# MachChinh.net
KiCad netlist of a schematic drawn in Altium Designer
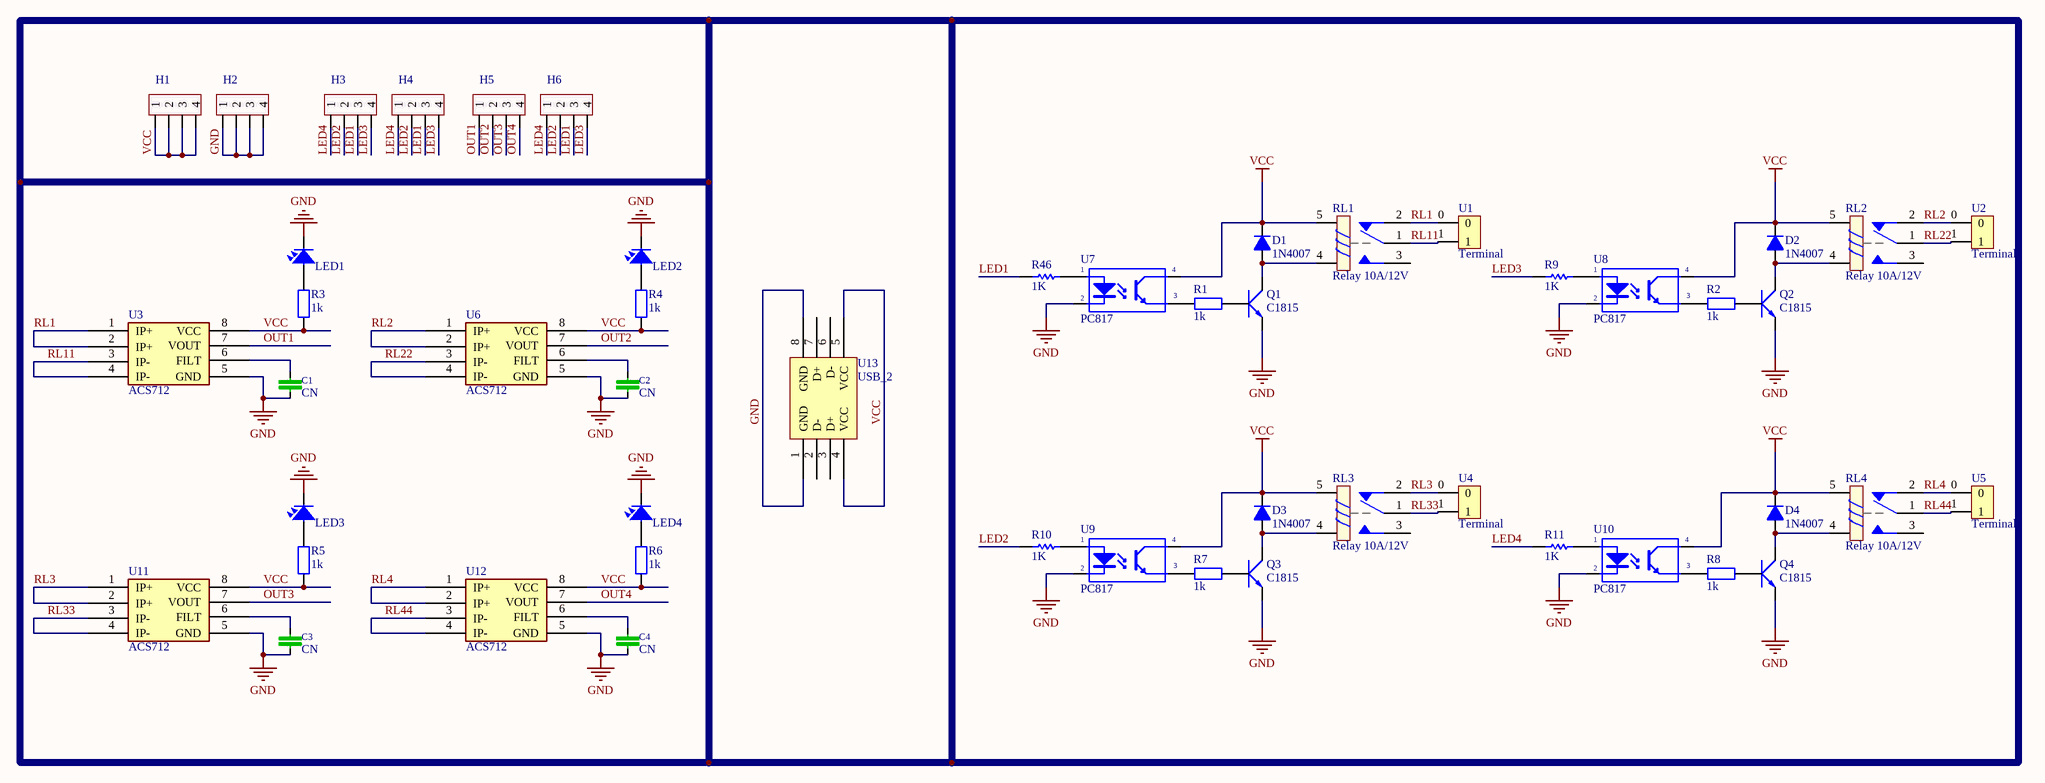
[diagram p0: MachChinh.SchDoc]

(export (version "E")
  (design (tool "Eeschema 10.0.6"))
  (components
    (comp (ref "C1")
      (value "CN")
      (footprint "C020-020,040")
      (description "CAP CER 0.047UF 25V X7R 0402")
      (libsource (lib "LIBRARY") (part "CN"))
    )
    (comp (ref "C2")
      (value "CN")
      (footprint "C020-020,040")
      (description "CAP CER 0.047UF 25V X7R 0402")
      (libsource (lib "LIBRARY") (part "CN"))
    )
    (comp (ref "C3")
      (value "CN")
      (footprint "C020-020,040")
      (description "CAP CER 0.047UF 25V X7R 0402")
      (libsource (lib "LIBRARY") (part "CN"))
    )
    (comp (ref "C4")
      (value "CN")
      (footprint "C020-020,040")
      (description "CAP CER 0.047UF 25V X7R 0402")
      (libsource (lib "LIBRARY") (part "CN"))
    )
    (comp (ref "D1")
      (value "1N4007")
      (footprint "D1A")
      (description "Diode 1A")
      (libsource (lib "syhaunguyen") (part "D1A"))
    )
    (comp (ref "D2")
      (value "1N4007")
      (footprint "D1A")
      (description "Diode 1A")
      (libsource (lib "syhaunguyen") (part "D1A"))
    )
    (comp (ref "D3")
      (value "1N4007")
      (footprint "D1A")
      (description "Diode 1A")
      (libsource (lib "syhaunguyen") (part "D1A"))
    )
    (comp (ref "D4")
      (value "1N4007")
      (footprint "D1A")
      (description "Diode 1A")
      (libsource (lib "syhaunguyen") (part "D1A"))
    )
    (comp (ref "H1")
      (value "Header4")
      (footprint "Header4")
      (description "Header IDC, 4 x 1 Pin Vertical 2.54mm Pitch (Non-Boxed, Male)")
      (libsource (lib "LIBRARY") (part "Header4"))
    )
    (comp (ref "H2")
      (value "Header4")
      (footprint "Header4")
      (description "Header IDC, 4 x 1 Pin Vertical 2.54mm Pitch (Non-Boxed, Male)")
      (libsource (lib "LIBRARY") (part "Header4"))
    )
    (comp (ref "H3")
      (value "Header4")
      (footprint "Header4")
      (description "Header IDC, 4 x 1 Pin Vertical 2.54mm Pitch (Non-Boxed, Male)")
      (libsource (lib "LIBRARY") (part "Header4"))
    )
    (comp (ref "H4")
      (value "Header4")
      (footprint "Header4")
      (description "Header IDC, 4 x 1 Pin Vertical 2.54mm Pitch (Non-Boxed, Male)")
      (libsource (lib "LIBRARY") (part "Header4"))
    )
    (comp (ref "H5")
      (value "Header4")
      (footprint "Header4")
      (description "Header IDC, 4 x 1 Pin Vertical 2.54mm Pitch (Non-Boxed, Male)")
      (libsource (lib "LIBRARY") (part "Header4"))
    )
    (comp (ref "H6")
      (value "Header4")
      (footprint "Header4")
      (description "Header IDC, 4 x 1 Pin Vertical 2.54mm Pitch (Non-Boxed, Male)")
      (libsource (lib "LIBRARY") (part "Header4"))
    )
    (comp (ref "LED1")
      (value "LED")
      (footprint "LED-3")
      (description "LED Single colour Green and Red")
      (libsource (lib "syhaunguyen") (part "LED"))
    )
    (comp (ref "LED2")
      (value "LED")
      (footprint "LED-3")
      (description "LED Single colour Green and Red")
      (libsource (lib "syhaunguyen") (part "LED"))
    )
    (comp (ref "LED3")
      (value "LED")
      (footprint "LED-3")
      (description "LED Single colour Green and Red")
      (libsource (lib "syhaunguyen") (part "LED"))
    )
    (comp (ref "LED4")
      (value "LED")
      (footprint "LED-3")
      (description "LED Single colour Green and Red")
      (libsource (lib "syhaunguyen") (part "LED"))
    )
    (comp (ref "Q1")
      (value "C1815")
      (footprint "QTO-92")
      (description "NPN 600mW, ECB")
      (libsource (lib "syhaunguyen") (part "C1815"))
    )
    (comp (ref "Q2")
      (value "C1815")
      (footprint "QTO-92")
      (description "NPN 600mW, ECB")
      (libsource (lib "syhaunguyen") (part "C1815"))
    )
    (comp (ref "Q3")
      (value "C1815")
      (footprint "QTO-92")
      (description "NPN 600mW, ECB")
      (libsource (lib "syhaunguyen") (part "C1815"))
    )
    (comp (ref "Q4")
      (value "C1815")
      (footprint "QTO-92")
      (description "NPN 600mW, ECB")
      (libsource (lib "syhaunguyen") (part "C1815"))
    )
    (comp (ref "R1")
      (value "1k")
      (footprint "R1/4W")
      (description "Resistor 1/4W")
      (libsource (lib "syhaunguyen") (part "R1/4W"))
    )
    (comp (ref "R2")
      (value "1k")
      (footprint "R1/4W")
      (description "Resistor 1/4W")
      (libsource (lib "syhaunguyen") (part "R1/4W"))
    )
    (comp (ref "R3")
      (value "1k")
      (footprint "R1/4W")
      (description "Resistor 1/4W")
      (libsource (lib "syhaunguyen") (part "R1/4W"))
    )
    (comp (ref "R4")
      (value "1k")
      (footprint "R1/4W")
      (description "Resistor 1/4W")
      (libsource (lib "syhaunguyen") (part "R1/4W"))
    )
    (comp (ref "R5")
      (value "1k")
      (footprint "R1/4W")
      (description "Resistor 1/4W")
      (libsource (lib "syhaunguyen") (part "R1/4W"))
    )
    (comp (ref "R6")
      (value "1k")
      (footprint "R1/4W")
      (description "Resistor 1/4W")
      (libsource (lib "syhaunguyen") (part "R1/4W"))
    )
    (comp (ref "R7")
      (value "1k")
      (footprint "R1/4W")
      (description "Resistor 1/4W")
      (libsource (lib "syhaunguyen") (part "R1/4W"))
    )
    (comp (ref "R8")
      (value "1k")
      (footprint "R1/4W")
      (description "Resistor 1/4W")
      (libsource (lib "syhaunguyen") (part "R1/4W"))
    )
    (comp (ref "R9")
      (value "1K")
      (footprint "R1/4W")
      (description "Resistor")
      (fields
        (field (name "MANUFACTURER") "Generic Components")
        (field (name "Comment") "Res1")
        (field (name "PUBLISHER") "Altium Hobart Technology Centre")
      )
      (libsource (lib "syhaunguyen") (part "Res1_4"))
    )
    (comp (ref "R10")
      (value "1K")
      (footprint "R1/4W")
      (description "Resistor")
      (fields
        (field (name "MANUFACTURER") "Generic Components")
        (field (name "Comment") "Res1")
        (field (name "PUBLISHER") "Altium Hobart Technology Centre")
      )
      (libsource (lib "syhaunguyen") (part "Res1_4"))
    )
    (comp (ref "R11")
      (value "1K")
      (footprint "R1/4W")
      (description "Resistor")
      (fields
        (field (name "MANUFACTURER") "Generic Components")
        (field (name "Comment") "Res1")
        (field (name "PUBLISHER") "Altium Hobart Technology Centre")
      )
      (libsource (lib "syhaunguyen") (part "Res1_4"))
    )
    (comp (ref "R46")
      (value "1K")
      (footprint "R1/4W")
      (description "Resistor")
      (fields
        (field (name "MANUFACTURER") "Generic Components")
        (field (name "Comment") "Res1")
        (field (name "PUBLISHER") "Altium Hobart Technology Centre")
      )
      (libsource (lib "syhaunguyen") (part "Res1_4"))
    )
    (comp (ref "RL1")
      (value "Relay 10A/12V")
      (footprint "RL_SPDT_10A")
      (description "Relay SPDT,10A - 12VDC 5 Pin")
      (libsource (lib "syhaunguyen") (part "Relay 1"))
    )
    (comp (ref "RL2")
      (value "Relay 10A/12V")
      (footprint "RL_SPDT_10A")
      (description "Relay SPDT,10A - 12VDC 5 Pin")
      (libsource (lib "syhaunguyen") (part "Relay 1"))
    )
    (comp (ref "RL3")
      (value "Relay 10A/12V")
      (footprint "RL_SPDT_10A")
      (description "Relay SPDT,10A - 12VDC 5 Pin")
      (libsource (lib "syhaunguyen") (part "Relay 1"))
    )
    (comp (ref "RL4")
      (value "Relay 10A/12V")
      (footprint "RL_SPDT_10A")
      (description "Relay SPDT,10A - 12VDC 5 Pin")
      (libsource (lib "syhaunguyen") (part "Relay 1"))
    )
    (comp (ref "U1")
      (value "Terminal")
      (footprint "TERMINAL5.08")
      (libsource (lib "THU_VIEN_PQB_Schlib1") (part "TERMINAL5.08"))
    )
    (comp (ref "U2")
      (value "Terminal")
      (footprint "TERMINAL5.08")
      (libsource (lib "THU_VIEN_PQB_Schlib1") (part "TERMINAL5.08"))
    )
    (comp (ref "U3")
      (value "ACS712")
      (footprint "ACS712")
      (libsource (lib "THU_VIEN_PQB_Schlib1") (part "ACS712"))
    )
    (comp (ref "U4")
      (value "Terminal")
      (footprint "TERMINAL5.08")
      (libsource (lib "THU_VIEN_PQB_Schlib1") (part "TERMINAL5.08"))
    )
    (comp (ref "U5")
      (value "Terminal")
      (footprint "TERMINAL5.08")
      (libsource (lib "THU_VIEN_PQB_Schlib1") (part "TERMINAL5.08"))
    )
    (comp (ref "U6")
      (value "ACS712")
      (footprint "ACS712")
      (libsource (lib "THU_VIEN_PQB_Schlib1") (part "ACS712"))
    )
    (comp (ref "U7")
      (value "PC817")
      (footprint "DIP4/W0.3")
      (description "Single Opto")
      (libsource (lib "syhaunguyen") (part "PC817"))
    )
    (comp (ref "U8")
      (value "PC817")
      (footprint "DIP4/W0.3")
      (description "Single Opto")
      (libsource (lib "syhaunguyen") (part "PC817"))
    )
    (comp (ref "U9")
      (value "PC817")
      (footprint "DIP4/W0.3")
      (description "Single Opto")
      (libsource (lib "syhaunguyen") (part "PC817"))
    )
    (comp (ref "U10")
      (value "PC817")
      (footprint "DIP4/W0.3")
      (description "Single Opto")
      (libsource (lib "syhaunguyen") (part "PC817"))
    )
    (comp (ref "U11")
      (value "ACS712")
      (footprint "ACS712")
      (libsource (lib "THU_VIEN_PQB_Schlib1") (part "ACS712"))
    )
    (comp (ref "U12")
      (value "ACS712")
      (footprint "ACS712")
      (libsource (lib "THU_VIEN_PQB_Schlib1") (part "ACS712"))
    )
    (comp (ref "U13")
      (value "USB_2")
      (footprint "USB_2")
      (description "USB")
      (libsource (lib "THU_VIEN_PQB_Schlib1") (part "USB_2"))
    )
  )
  (nets
    (net (code "1") (name "/LED1") (class "Default")
      (node (ref "H3") (pin "3") (pinfunction "3_3") (pintype "passive"))
      (node (ref "H4") (pin "3") (pinfunction "3_3") (pintype "passive"))
      (node (ref "H6") (pin "3") (pinfunction "3_3") (pintype "passive"))
      (node (ref "R46") (pin "2") (pinfunction "2_2") (pintype "passive"))
    )
    (net (code "2") (name "/LED2") (class "Default")
      (node (ref "H3") (pin "2") (pinfunction "2_2") (pintype "passive"))
      (node (ref "H4") (pin "2") (pinfunction "2_2") (pintype "passive"))
      (node (ref "H6") (pin "2") (pinfunction "2_2") (pintype "passive"))
      (node (ref "R10") (pin "2") (pinfunction "2_2") (pintype "passive"))
    )
    (net (code "3") (name "/LED3") (class "Default")
      (node (ref "H3") (pin "4") (pinfunction "4_4") (pintype "passive"))
      (node (ref "H4") (pin "4") (pinfunction "4_4") (pintype "passive"))
      (node (ref "H6") (pin "4") (pinfunction "4_4") (pintype "passive"))
      (node (ref "R9") (pin "2") (pinfunction "2_2") (pintype "passive"))
    )
    (net (code "4") (name "/LED4") (class "Default")
      (node (ref "H3") (pin "1") (pinfunction "1_1") (pintype "passive"))
      (node (ref "H4") (pin "1") (pinfunction "1_1") (pintype "passive"))
      (node (ref "H6") (pin "1") (pinfunction "1_1") (pintype "passive"))
      (node (ref "R11") (pin "2") (pinfunction "2_2") (pintype "passive"))
    )
    (net (code "5") (name "/OUT1") (class "Default")
      (node (ref "H5") (pin "1") (pinfunction "1_1") (pintype "passive"))
      (node (ref "U3") (pin "7") (pinfunction "VOUT_7") (pintype "passive"))
    )
    (net (code "6") (name "/OUT2") (class "Default")
      (node (ref "H5") (pin "2") (pinfunction "2_2") (pintype "passive"))
      (node (ref "U6") (pin "7") (pinfunction "VOUT_7") (pintype "passive"))
    )
    (net (code "7") (name "/OUT3") (class "Default")
      (node (ref "H5") (pin "3") (pinfunction "3_3") (pintype "passive"))
      (node (ref "U11") (pin "7") (pinfunction "VOUT_7") (pintype "passive"))
    )
    (net (code "8") (name "/OUT4") (class "Default")
      (node (ref "H5") (pin "4") (pinfunction "4_4") (pintype "passive"))
      (node (ref "U12") (pin "7") (pinfunction "VOUT_7") (pintype "passive"))
    )
    (net (code "9") (name "/RL1") (class "Default")
      (node (ref "RL1") (pin "2") (pinfunction "2_2") (pintype "passive"))
      (node (ref "U1") (pin "0") (pinfunction "0_0") (pintype "passive"))
      (node (ref "U3") (pin "1") (pinfunction "IP+_1") (pintype "passive"))
      (node (ref "U3") (pin "2") (pinfunction "IP+_2") (pintype "passive"))
    )
    (net (code "10") (name "/RL2") (class "Default")
      (node (ref "RL2") (pin "2") (pinfunction "2_2") (pintype "passive"))
      (node (ref "U2") (pin "0") (pinfunction "0_0") (pintype "passive"))
      (node (ref "U6") (pin "1") (pinfunction "IP+_1") (pintype "passive"))
      (node (ref "U6") (pin "2") (pinfunction "IP+_2") (pintype "passive"))
    )
    (net (code "11") (name "/RL3") (class "Default")
      (node (ref "RL3") (pin "2") (pinfunction "2_2") (pintype "passive"))
      (node (ref "U11") (pin "1") (pinfunction "IP+_1") (pintype "passive"))
      (node (ref "U11") (pin "2") (pinfunction "IP+_2") (pintype "passive"))
      (node (ref "U4") (pin "0") (pinfunction "0_0") (pintype "passive"))
    )
    (net (code "12") (name "/RL4") (class "Default")
      (node (ref "RL4") (pin "2") (pinfunction "2_2") (pintype "passive"))
      (node (ref "U12") (pin "1") (pinfunction "IP+_1") (pintype "passive"))
      (node (ref "U12") (pin "2") (pinfunction "IP+_2") (pintype "passive"))
      (node (ref "U5") (pin "0") (pinfunction "0_0") (pintype "passive"))
    )
    (net (code "13") (name "/RL11") (class "Default")
      (node (ref "RL1") (pin "1") (pinfunction "1_1") (pintype "passive"))
      (node (ref "U1") (pin "1") (pinfunction "1_1") (pintype "passive"))
      (node (ref "U3") (pin "3") (pinfunction "IP-_3") (pintype "passive"))
      (node (ref "U3") (pin "4") (pinfunction "IP-_4") (pintype "passive"))
    )
    (net (code "14") (name "/RL22") (class "Default")
      (node (ref "RL2") (pin "1") (pinfunction "1_1") (pintype "passive"))
      (node (ref "U2") (pin "1") (pinfunction "1_1") (pintype "passive"))
      (node (ref "U6") (pin "3") (pinfunction "IP-_3") (pintype "passive"))
      (node (ref "U6") (pin "4") (pinfunction "IP-_4") (pintype "passive"))
    )
    (net (code "15") (name "/RL33") (class "Default")
      (node (ref "RL3") (pin "1") (pinfunction "1_1") (pintype "passive"))
      (node (ref "U11") (pin "3") (pinfunction "IP-_3") (pintype "passive"))
      (node (ref "U11") (pin "4") (pinfunction "IP-_4") (pintype "passive"))
      (node (ref "U4") (pin "1") (pinfunction "1_1") (pintype "passive"))
    )
    (net (code "16") (name "/RL44") (class "Default")
      (node (ref "RL4") (pin "1") (pinfunction "1_1") (pintype "passive"))
      (node (ref "U12") (pin "3") (pinfunction "IP-_3") (pintype "passive"))
      (node (ref "U12") (pin "4") (pinfunction "IP-_4") (pintype "passive"))
      (node (ref "U5") (pin "1") (pinfunction "1_1") (pintype "passive"))
    )
    (net (code "17") (name "GND") (class "Default")
      (node (ref "C1") (pin "2") (pinfunction "2_2") (pintype "passive"))
      (node (ref "C2") (pin "2") (pinfunction "2_2") (pintype "passive"))
      (node (ref "C3") (pin "2") (pinfunction "2_2") (pintype "passive"))
      (node (ref "C4") (pin "2") (pinfunction "2_2") (pintype "passive"))
      (node (ref "H2") (pin "1") (pinfunction "1_1") (pintype "passive"))
      (node (ref "H2") (pin "2") (pinfunction "2_2") (pintype "passive"))
      (node (ref "H2") (pin "3") (pinfunction "3_3") (pintype "passive"))
      (node (ref "H2") (pin "4") (pinfunction "4_4") (pintype "passive"))
      (node (ref "LED1") (pin "2") (pinfunction "2_2") (pintype "passive"))
      (node (ref "LED2") (pin "2") (pinfunction "2_2") (pintype "passive"))
      (node (ref "LED3") (pin "2") (pinfunction "2_2") (pintype "passive"))
      (node (ref "LED4") (pin "2") (pinfunction "2_2") (pintype "passive"))
      (node (ref "Q1") (pin "1") (pinfunction "E_1") (pintype "passive"))
      (node (ref "Q2") (pin "1") (pinfunction "E_1") (pintype "passive"))
      (node (ref "Q3") (pin "1") (pinfunction "E_1") (pintype "passive"))
      (node (ref "Q4") (pin "1") (pinfunction "E_1") (pintype "passive"))
      (node (ref "U10") (pin "2") (pinfunction "K_2") (pintype "passive"))
      (node (ref "U11") (pin "5") (pinfunction "GND_5") (pintype "passive"))
      (node (ref "U12") (pin "5") (pinfunction "GND_5") (pintype "passive"))
      (node (ref "U13") (pin "1") (pinfunction "GND_1") (pintype "passive"))
      (node (ref "U13") (pin "8") (pinfunction "GND_8") (pintype "passive"))
      (node (ref "U3") (pin "5") (pinfunction "GND_5") (pintype "passive"))
      (node (ref "U6") (pin "5") (pinfunction "GND_5") (pintype "passive"))
      (node (ref "U7") (pin "2") (pinfunction "K_2") (pintype "passive"))
      (node (ref "U8") (pin "2") (pinfunction "K_2") (pintype "passive"))
      (node (ref "U9") (pin "2") (pinfunction "K_2") (pintype "passive"))
    )
    (net (code "18") (name "Net-(D1-A)") (class "Default")
      (node (ref "D1") (pin "1") (pinfunction "A_1") (pintype "passive"))
      (node (ref "Q1") (pin "2") (pinfunction "C_2") (pintype "passive"))
      (node (ref "RL1") (pin "4") (pinfunction "4_4") (pintype "passive"))
    )
    (net (code "19") (name "Net-(D2-A)") (class "Default")
      (node (ref "D2") (pin "1") (pinfunction "A_1") (pintype "passive"))
      (node (ref "Q2") (pin "2") (pinfunction "C_2") (pintype "passive"))
      (node (ref "RL2") (pin "4") (pinfunction "4_4") (pintype "passive"))
    )
    (net (code "20") (name "Net-(D3-A)") (class "Default")
      (node (ref "D3") (pin "1") (pinfunction "A_1") (pintype "passive"))
      (node (ref "Q3") (pin "2") (pinfunction "C_2") (pintype "passive"))
      (node (ref "RL3") (pin "4") (pinfunction "4_4") (pintype "passive"))
    )
    (net (code "21") (name "Net-(D4-A)") (class "Default")
      (node (ref "D4") (pin "1") (pinfunction "A_1") (pintype "passive"))
      (node (ref "Q4") (pin "2") (pinfunction "C_2") (pintype "passive"))
      (node (ref "RL4") (pin "4") (pinfunction "4_4") (pintype "passive"))
    )
    (net (code "22") (name "Net-(LED1-Pad1)") (class "Default")
      (node (ref "LED1") (pin "1") (pinfunction "1_1") (pintype "passive"))
      (node (ref "R3") (pin "2") (pinfunction "2_2") (pintype "passive"))
    )
    (net (code "23") (name "Net-(LED2-Pad1)") (class "Default")
      (node (ref "LED2") (pin "1") (pinfunction "1_1") (pintype "passive"))
      (node (ref "R4") (pin "2") (pinfunction "2_2") (pintype "passive"))
    )
    (net (code "24") (name "Net-(LED3-Pad1)") (class "Default")
      (node (ref "LED3") (pin "1") (pinfunction "1_1") (pintype "passive"))
      (node (ref "R5") (pin "2") (pinfunction "2_2") (pintype "passive"))
    )
    (net (code "25") (name "Net-(LED4-Pad1)") (class "Default")
      (node (ref "LED4") (pin "1") (pinfunction "1_1") (pintype "passive"))
      (node (ref "R6") (pin "2") (pinfunction "2_2") (pintype "passive"))
    )
    (net (code "26") (name "Net-(Q1-B)") (class "Default")
      (node (ref "Q1") (pin "3") (pinfunction "B_3") (pintype "passive"))
      (node (ref "R1") (pin "2") (pinfunction "2_2") (pintype "passive"))
    )
    (net (code "27") (name "Net-(Q2-B)") (class "Default")
      (node (ref "Q2") (pin "3") (pinfunction "B_3") (pintype "passive"))
      (node (ref "R2") (pin "2") (pinfunction "2_2") (pintype "passive"))
    )
    (net (code "28") (name "Net-(Q3-B)") (class "Default")
      (node (ref "Q3") (pin "3") (pinfunction "B_3") (pintype "passive"))
      (node (ref "R7") (pin "2") (pinfunction "2_2") (pintype "passive"))
    )
    (net (code "29") (name "Net-(Q4-B)") (class "Default")
      (node (ref "Q4") (pin "3") (pinfunction "B_3") (pintype "passive"))
      (node (ref "R8") (pin "2") (pinfunction "2_2") (pintype "passive"))
    )
    (net (code "30") (name "Net-(U3-FILT)") (class "Default")
      (node (ref "C1") (pin "1") (pinfunction "1_1") (pintype "passive"))
      (node (ref "U3") (pin "6") (pinfunction "FILT_6") (pintype "passive"))
    )
    (net (code "31") (name "Net-(U6-FILT)") (class "Default")
      (node (ref "C2") (pin "1") (pinfunction "1_1") (pintype "passive"))
      (node (ref "U6") (pin "6") (pinfunction "FILT_6") (pintype "passive"))
    )
    (net (code "32") (name "Net-(U7-A)") (class "Default")
      (node (ref "R46") (pin "1") (pinfunction "1_1") (pintype "passive"))
      (node (ref "U7") (pin "1") (pinfunction "A_1") (pintype "passive"))
    )
    (net (code "33") (name "Net-(U7-E)") (class "Default")
      (node (ref "R1") (pin "1") (pinfunction "1_1") (pintype "passive"))
      (node (ref "U7") (pin "3") (pinfunction "E_3") (pintype "passive"))
    )
    (net (code "34") (name "Net-(U8-A)") (class "Default")
      (node (ref "R9") (pin "1") (pinfunction "1_1") (pintype "passive"))
      (node (ref "U8") (pin "1") (pinfunction "A_1") (pintype "passive"))
    )
    (net (code "35") (name "Net-(U8-E)") (class "Default")
      (node (ref "R2") (pin "1") (pinfunction "1_1") (pintype "passive"))
      (node (ref "U8") (pin "3") (pinfunction "E_3") (pintype "passive"))
    )
    (net (code "36") (name "Net-(U9-A)") (class "Default")
      (node (ref "R10") (pin "1") (pinfunction "1_1") (pintype "passive"))
      (node (ref "U9") (pin "1") (pinfunction "A_1") (pintype "passive"))
    )
    (net (code "37") (name "Net-(U9-E)") (class "Default")
      (node (ref "R7") (pin "1") (pinfunction "1_1") (pintype "passive"))
      (node (ref "U9") (pin "3") (pinfunction "E_3") (pintype "passive"))
    )
    (net (code "38") (name "Net-(U10-A)") (class "Default")
      (node (ref "R11") (pin "1") (pinfunction "1_1") (pintype "passive"))
      (node (ref "U10") (pin "1") (pinfunction "A_1") (pintype "passive"))
    )
    (net (code "39") (name "Net-(U10-E)") (class "Default")
      (node (ref "R8") (pin "1") (pinfunction "1_1") (pintype "passive"))
      (node (ref "U10") (pin "3") (pinfunction "E_3") (pintype "passive"))
    )
    (net (code "40") (name "Net-(U11-FILT)") (class "Default")
      (node (ref "C3") (pin "1") (pinfunction "1_1") (pintype "passive"))
      (node (ref "U11") (pin "6") (pinfunction "FILT_6") (pintype "passive"))
    )
    (net (code "41") (name "Net-(U12-FILT)") (class "Default")
      (node (ref "C4") (pin "1") (pinfunction "1_1") (pintype "passive"))
      (node (ref "U12") (pin "6") (pinfunction "FILT_6") (pintype "passive"))
    )
    (net (code "42") (name "VCC") (class "Default")
      (node (ref "D1") (pin "2") (pinfunction "K_2") (pintype "passive"))
      (node (ref "D2") (pin "2") (pinfunction "K_2") (pintype "passive"))
      (node (ref "D3") (pin "2") (pinfunction "K_2") (pintype "passive"))
      (node (ref "D4") (pin "2") (pinfunction "K_2") (pintype "passive"))
      (node (ref "H1") (pin "1") (pinfunction "1_1") (pintype "passive"))
      (node (ref "H1") (pin "2") (pinfunction "2_2") (pintype "passive"))
      (node (ref "H1") (pin "3") (pinfunction "3_3") (pintype "passive"))
      (node (ref "H1") (pin "4") (pinfunction "4_4") (pintype "passive"))
      (node (ref "R3") (pin "1") (pinfunction "1_1") (pintype "passive"))
      (node (ref "R4") (pin "1") (pinfunction "1_1") (pintype "passive"))
      (node (ref "R5") (pin "1") (pinfunction "1_1") (pintype "passive"))
      (node (ref "R6") (pin "1") (pinfunction "1_1") (pintype "passive"))
      (node (ref "RL1") (pin "5") (pinfunction "5_5") (pintype "passive"))
      (node (ref "RL2") (pin "5") (pinfunction "5_5") (pintype "passive"))
      (node (ref "RL3") (pin "5") (pinfunction "5_5") (pintype "passive"))
      (node (ref "RL4") (pin "5") (pinfunction "5_5") (pintype "passive"))
      (node (ref "U10") (pin "4") (pinfunction "C_4") (pintype "passive"))
      (node (ref "U11") (pin "8") (pinfunction "VCC_8") (pintype "passive"))
      (node (ref "U12") (pin "8") (pinfunction "VCC_8") (pintype "passive"))
      (node (ref "U13") (pin "4") (pinfunction "VCC_4") (pintype "passive"))
      (node (ref "U13") (pin "5") (pinfunction "VCC_5") (pintype "passive"))
      (node (ref "U3") (pin "8") (pinfunction "VCC_8") (pintype "passive"))
      (node (ref "U6") (pin "8") (pinfunction "VCC_8") (pintype "passive"))
      (node (ref "U7") (pin "4") (pinfunction "C_4") (pintype "passive"))
      (node (ref "U8") (pin "4") (pinfunction "C_4") (pintype "passive"))
      (node (ref "U9") (pin "4") (pinfunction "C_4") (pintype "passive"))
    )
    (net (code "43") (name "unconnected-(RL1-Pad3)") (class "Default")
      (node (ref "RL1") (pin "3") (pinfunction "3_3") (pintype "passive"))
    )
    (net (code "44") (name "unconnected-(RL2-Pad3)") (class "Default")
      (node (ref "RL2") (pin "3") (pinfunction "3_3") (pintype "passive"))
    )
    (net (code "45") (name "unconnected-(RL3-Pad3)") (class "Default")
      (node (ref "RL3") (pin "3") (pinfunction "3_3") (pintype "passive"))
    )
    (net (code "46") (name "unconnected-(RL4-Pad3)") (class "Default")
      (node (ref "RL4") (pin "3") (pinfunction "3_3") (pintype "passive"))
    )
    (net (code "47") (name "unconnected-(U13-D+-Pad3)") (class "Default")
      (node (ref "U13") (pin "3") (pinfunction "D+_3") (pintype "passive"))
    )
    (net (code "48") (name "unconnected-(U13-D+-Pad7)") (class "Default")
      (node (ref "U13") (pin "7") (pinfunction "D+_7") (pintype "passive"))
    )
    (net (code "49") (name "unconnected-(U13-D--Pad2)") (class "Default")
      (node (ref "U13") (pin "2") (pinfunction "D-_2") (pintype "passive"))
    )
    (net (code "50") (name "unconnected-(U13-D--Pad6)") (class "Default")
      (node (ref "U13") (pin "6") (pinfunction "D-_6") (pintype "passive"))
    )
  )
)
